# wlpkt1_zas.net
KiCad netlist of a schematic drawn in Altium Designer
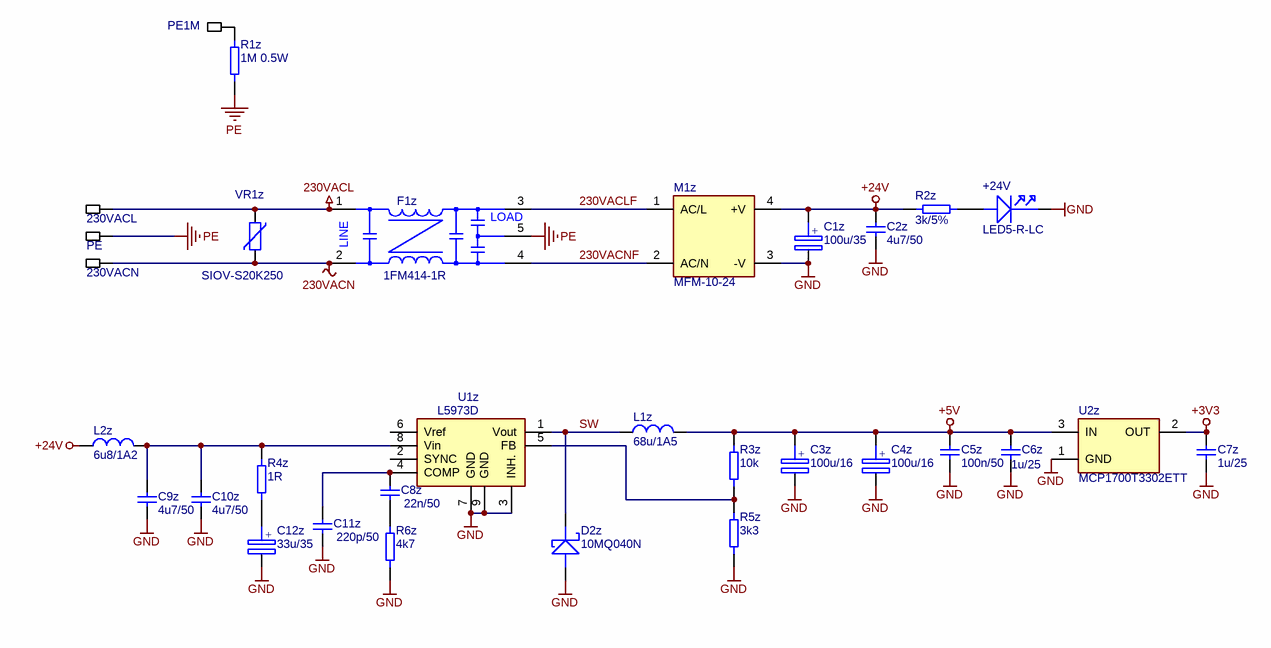
[diagram p0: wlpkt1_zas.SchDoc]

(export (version "E")
  (design (tool "Eeschema 10.0.6"))
  (components
    (comp (ref "+24V") (value "LED5-R-LC") (footprint "CO26") (libsource (lib "PartsMySQL") (part "LED")))
    (comp (ref "230VACL")
      (value "PAD1_5MM")
      (footprint "PAD1_5MM")
      (libsource (lib "PartsMySQL") (part "CLAMP_NOBOM"))
    )
    (comp (ref "230VACN")
      (value "PAD1_5MM")
      (footprint "PAD1_5MM")
      (libsource (lib "PartsMySQL") (part "CLAMP_NOBOM"))
    )
    (comp (ref "C1z") (value "100u/35") (footprint "CE1028") (libsource (lib "PartsMySQL") (part "CEL")))
    (comp (ref "C2z") (value "4u7/50") (footprint "1210") (libsource (lib "PartsMySQL") (part "C")))
    (comp (ref "C3z") (value "100u/16") (footprint "CEL7343-43") (libsource (lib "PartsMySQL") (part "CEL")))
    (comp (ref "C4z") (value "100u/16") (footprint "CEL7343-43") (libsource (lib "PartsMySQL") (part "CEL")))
    (comp (ref "C5z") (value "100n/50") (footprint "0805") (libsource (lib "PartsMySQL") (part "C")))
    (comp (ref "C6z") (value "1u/25") (footprint "0805") (libsource (lib "PartsMySQL") (part "C")))
    (comp (ref "C7z") (value "1u/25") (footprint "0805") (libsource (lib "PartsMySQL") (part "C")))
    (comp (ref "C8z") (value "22n/50") (footprint "0603-IPC") (libsource (lib "PartsMySQL") (part "C")))
    (comp (ref "C9z") (value "4u7/50") (footprint "1210") (libsource (lib "PartsMySQL") (part "C")))
    (comp (ref "C10z") (value "4u7/50") (footprint "1210") (libsource (lib "PartsMySQL") (part "C")))
    (comp (ref "C11z") (value "220p/50") (footprint "0603-IPC") (libsource (lib "PartsMySQL") (part "C")))
    (comp (ref "C12z") (value "33u/35") (footprint "CEL7343-31") (libsource (lib "PartsMySQL") (part "CEL")))
    (comp (ref "D2z")
      (value "10MQ040N")
      (footprint "SMA")
      (libsource (lib "PartsMySQL") (part "DIODE_SCHOTTKY"))
    )
    (comp (ref "F1z") (value "1FM414-1R") (footprint "1FM414") (libsource (lib "PartsMySQL") (part "1FM414")))
    (comp (ref "L1z")
      (value "68u/1A5")
      (footprint "SRR1208")
      (libsource (lib "PartsMySQL") (part "INDUCTOR"))
    )
    (comp (ref "L2z") (value "6u8/1A2") (footprint "WE-PD3") (libsource (lib "PartsMySQL") (part "INDUCTOR")))
    (comp (ref "M1z")
      (value "MFM-10-24")
      (footprint "MFM-10-24")
      (libsource (lib "PartsMySQL") (part "PM-10-5"))
    )
    (comp (ref "PE")
      (value "PAD1_5MM")
      (footprint "PAD1_5MM")
      (libsource (lib "PartsMySQL") (part "CLAMP_NOBOM"))
    )
    (comp (ref "PE1M")
      (value "PAD1_5MM")
      (footprint "PAD1_5MM")
      (libsource (lib "PartsMySQL") (part "CLAMP_NOBOM"))
    )
    (comp (ref "R1z") (value "1M 0.5W") (footprint "R502816") (libsource (lib "PartsMySQL") (part "R")))
    (comp (ref "R2z") (value "3k/5%") (footprint "R402510V") (libsource (lib "PartsMySQL") (part "R")))
    (comp (ref "R3z") (value "10k") (footprint "0805R") (libsource (lib "PartsMySQL") (part "R")))
    (comp (ref "R4z") (value "1R") (footprint "R402510") (libsource (lib "PartsMySQL") (part "R")))
    (comp (ref "R5z") (value "3k3") (footprint "0805R") (libsource (lib "PartsMySQL") (part "R")))
    (comp (ref "R6z") (value "4k7") (footprint "0603R") (libsource (lib "PartsMySQL") (part "R")))
    (comp (ref "U1z") (value "L5973D") (footprint "HSOP8") (libsource (lib "PartsMySQL") (part "L5973")))
    (comp (ref "U2z")
      (value "MCP1700T3302ETT")
      (footprint "SOT23-3")
      (libsource (lib "PartsMySQL") (part "MCP1700"))
    )
    (comp (ref "VR1z")
      (value "SIOV-S20K250")
      (footprint "SIOV-S20K275")
      (libsource (lib "PartsMySQL") (part "VARISTOR"))
    )
  )
  (nets
    (net (code "1") (name "+3V3") (class "Default")
      (node (ref "C7z") (pin "1") (pinfunction "1_1") (pintype "passive"))
      (node (ref "U2z") (pin "2") (pinfunction "OUT_2") (pintype "passive"))
    )
    (net (code "2") (name "+5V") (class "Default")
      (node (ref "C3z") (pin "2") (pinfunction "2_2") (pintype "passive"))
      (node (ref "C4z") (pin "2") (pinfunction "2_2") (pintype "passive"))
      (node (ref "C5z") (pin "2") (pinfunction "2_2") (pintype "passive"))
      (node (ref "C6z") (pin "1") (pinfunction "1_1") (pintype "passive"))
      (node (ref "L1z") (pin "2") (pinfunction "2_2") (pintype "passive"))
      (node (ref "R3z") (pin "1") (pinfunction "1_1") (pintype "passive"))
      (node (ref "U2z") (pin "3") (pinfunction "IN_3") (pintype "passive"))
    )
    (net (code "3") (name "+24V") (class "Default")
      (node (ref "C1z") (pin "2") (pinfunction "2_2") (pintype "passive"))
      (node (ref "C2z") (pin "1") (pinfunction "1_1") (pintype "passive"))
      (node (ref "L2z") (pin "1") (pinfunction "1_1") (pintype "passive"))
      (node (ref "M1z") (pin "4") (pinfunction "+V_4") (pintype "passive"))
      (node (ref "R2z") (pin "1") (pinfunction "1_1") (pintype "passive"))
    )
    (net (code "4") (name "/230VACLF") (class "Default")
      (node (ref "F1z") (pin "3") (pinfunction "OUT2_3") (pintype "passive"))
      (node (ref "M1z") (pin "1") (pinfunction "AC/L_1") (pintype "passive"))
    )
    (net (code "5") (name "/230VACNF") (class "Default")
      (node (ref "F1z") (pin "4") (pinfunction "OUT1_4") (pintype "passive"))
      (node (ref "M1z") (pin "2") (pinfunction "AC/N_2") (pintype "passive"))
    )
    (net (code "6") (name "/SW") (class "Default")
      (node (ref "D2z") (pin "1") (pinfunction "CATH_1") (pintype "passive"))
      (node (ref "L1z") (pin "1") (pinfunction "1_1") (pintype "passive"))
      (node (ref "U1z") (pin "1") (pinfunction "Vout_1") (pintype "passive"))
    )
    (net (code "7") (name "230VACL") (class "Default")
      (node (ref "230VACL") (pin "1") (pinfunction "1_1") (pintype "passive"))
      (node (ref "F1z") (pin "1") (pinfunction "IN1_1") (pintype "passive"))
      (node (ref "VR1z") (pin "1") (pinfunction "1_1") (pintype "passive"))
    )
    (net (code "8") (name "230VACN") (class "Default")
      (node (ref "230VACN") (pin "1") (pinfunction "1_1") (pintype "passive"))
      (node (ref "F1z") (pin "2") (pinfunction "IN2_2") (pintype "passive"))
      (node (ref "VR1z") (pin "2") (pinfunction "2_2") (pintype "passive"))
    )
    (net (code "9") (name "GND") (class "Default")
      (node (ref "+24V") (pin "CATH") (pinfunction "CATH_CATH") (pintype "passive"))
      (node (ref "C10z") (pin "2") (pinfunction "2_2") (pintype "passive"))
      (node (ref "C11z") (pin "2") (pinfunction "2_2") (pintype "passive"))
      (node (ref "C12z") (pin "1") (pinfunction "1_1") (pintype "passive"))
      (node (ref "C1z") (pin "1") (pinfunction "1_1") (pintype "passive"))
      (node (ref "C2z") (pin "2") (pinfunction "2_2") (pintype "passive"))
      (node (ref "C3z") (pin "1") (pinfunction "1_1") (pintype "passive"))
      (node (ref "C4z") (pin "1") (pinfunction "1_1") (pintype "passive"))
      (node (ref "C5z") (pin "1") (pinfunction "1_1") (pintype "passive"))
      (node (ref "C6z") (pin "2") (pinfunction "2_2") (pintype "passive"))
      (node (ref "C7z") (pin "2") (pinfunction "2_2") (pintype "passive"))
      (node (ref "C9z") (pin "2") (pinfunction "2_2") (pintype "passive"))
      (node (ref "D2z") (pin "2") (pinfunction "ANOD_2") (pintype "passive"))
      (node (ref "M1z") (pin "3") (pinfunction "-V_3") (pintype "passive"))
      (node (ref "R5z") (pin "2") (pinfunction "2_2") (pintype "passive"))
      (node (ref "R6z") (pin "2") (pinfunction "2_2") (pintype "passive"))
      (node (ref "U1z") (pin "3") (pinfunction "INH._3") (pintype "passive"))
      (node (ref "U1z") (pin "7") (pinfunction "GND_7") (pintype "passive"))
      (node (ref "U1z") (pin "9") (pinfunction "GND_9") (pintype "passive"))
      (node (ref "U2z") (pin "1") (pinfunction "GND_1") (pintype "passive"))
    )
    (net (code "10") (name "Net-(+24V-PadANOD)") (class "Default")
      (node (ref "+24V") (pin "ANOD") (pinfunction "ANOD_ANOD") (pintype "passive"))
      (node (ref "R2z") (pin "2") (pinfunction "2_2") (pintype "passive"))
    )
    (net (code "11") (name "Net-(C8z-Pad2)") (class "Default")
      (node (ref "C8z") (pin "2") (pinfunction "2_2") (pintype "passive"))
      (node (ref "R6z") (pin "1") (pinfunction "1_1") (pintype "passive"))
    )
    (net (code "12") (name "Net-(C12z-Pad2)") (class "Default")
      (node (ref "C12z") (pin "2") (pinfunction "2_2") (pintype "passive"))
      (node (ref "R4z") (pin "2") (pinfunction "2_2") (pintype "passive"))
    )
    (net (code "13") (name "Net-(PE1M-Pad1)") (class "Default")
      (node (ref "PE1M") (pin "1") (pinfunction "1_1") (pintype "passive"))
      (node (ref "R1z") (pin "2") (pinfunction "2_2") (pintype "passive"))
    )
    (net (code "14") (name "Net-(U1z-COMP)") (class "Default")
      (node (ref "C11z") (pin "1") (pinfunction "1_1") (pintype "passive"))
      (node (ref "C8z") (pin "1") (pinfunction "1_1") (pintype "passive"))
      (node (ref "U1z") (pin "4") (pinfunction "COMP_4") (pintype "passive"))
    )
    (net (code "15") (name "Net-(U1z-FB)") (class "Default")
      (node (ref "R3z") (pin "2") (pinfunction "2_2") (pintype "passive"))
      (node (ref "R5z") (pin "1") (pinfunction "1_1") (pintype "passive"))
      (node (ref "U1z") (pin "5") (pinfunction "FB_5") (pintype "passive"))
    )
    (net (code "16") (name "Net-(U1z-Vin)") (class "Default")
      (node (ref "C10z") (pin "1") (pinfunction "1_1") (pintype "passive"))
      (node (ref "C9z") (pin "1") (pinfunction "1_1") (pintype "passive"))
      (node (ref "L2z") (pin "2") (pinfunction "2_2") (pintype "passive"))
      (node (ref "R4z") (pin "1") (pinfunction "1_1") (pintype "passive"))
      (node (ref "U1z") (pin "8") (pinfunction "Vin_8") (pintype "passive"))
    )
    (net (code "17") (name "PE") (class "Default")
      (node (ref "F1z") (pin "5") (pinfunction "5_5") (pintype "passive"))
      (node (ref "PE") (pin "1") (pinfunction "1_1") (pintype "passive"))
      (node (ref "R1z") (pin "1") (pinfunction "1_1") (pintype "passive"))
    )
    (net (code "18") (name "unconnected-(U1z-SYNC-Pad2)") (class "Default")
      (node (ref "U1z") (pin "2") (pinfunction "SYNC_2") (pintype "passive"))
    )
    (net (code "19") (name "unconnected-(U1z-Vref-Pad6)") (class "Default")
      (node (ref "U1z") (pin "6") (pinfunction "Vref_6") (pintype "passive"))
    )
  )
)
